# untitled.net
KiCad netlist of a schematic drawn in EAGLE
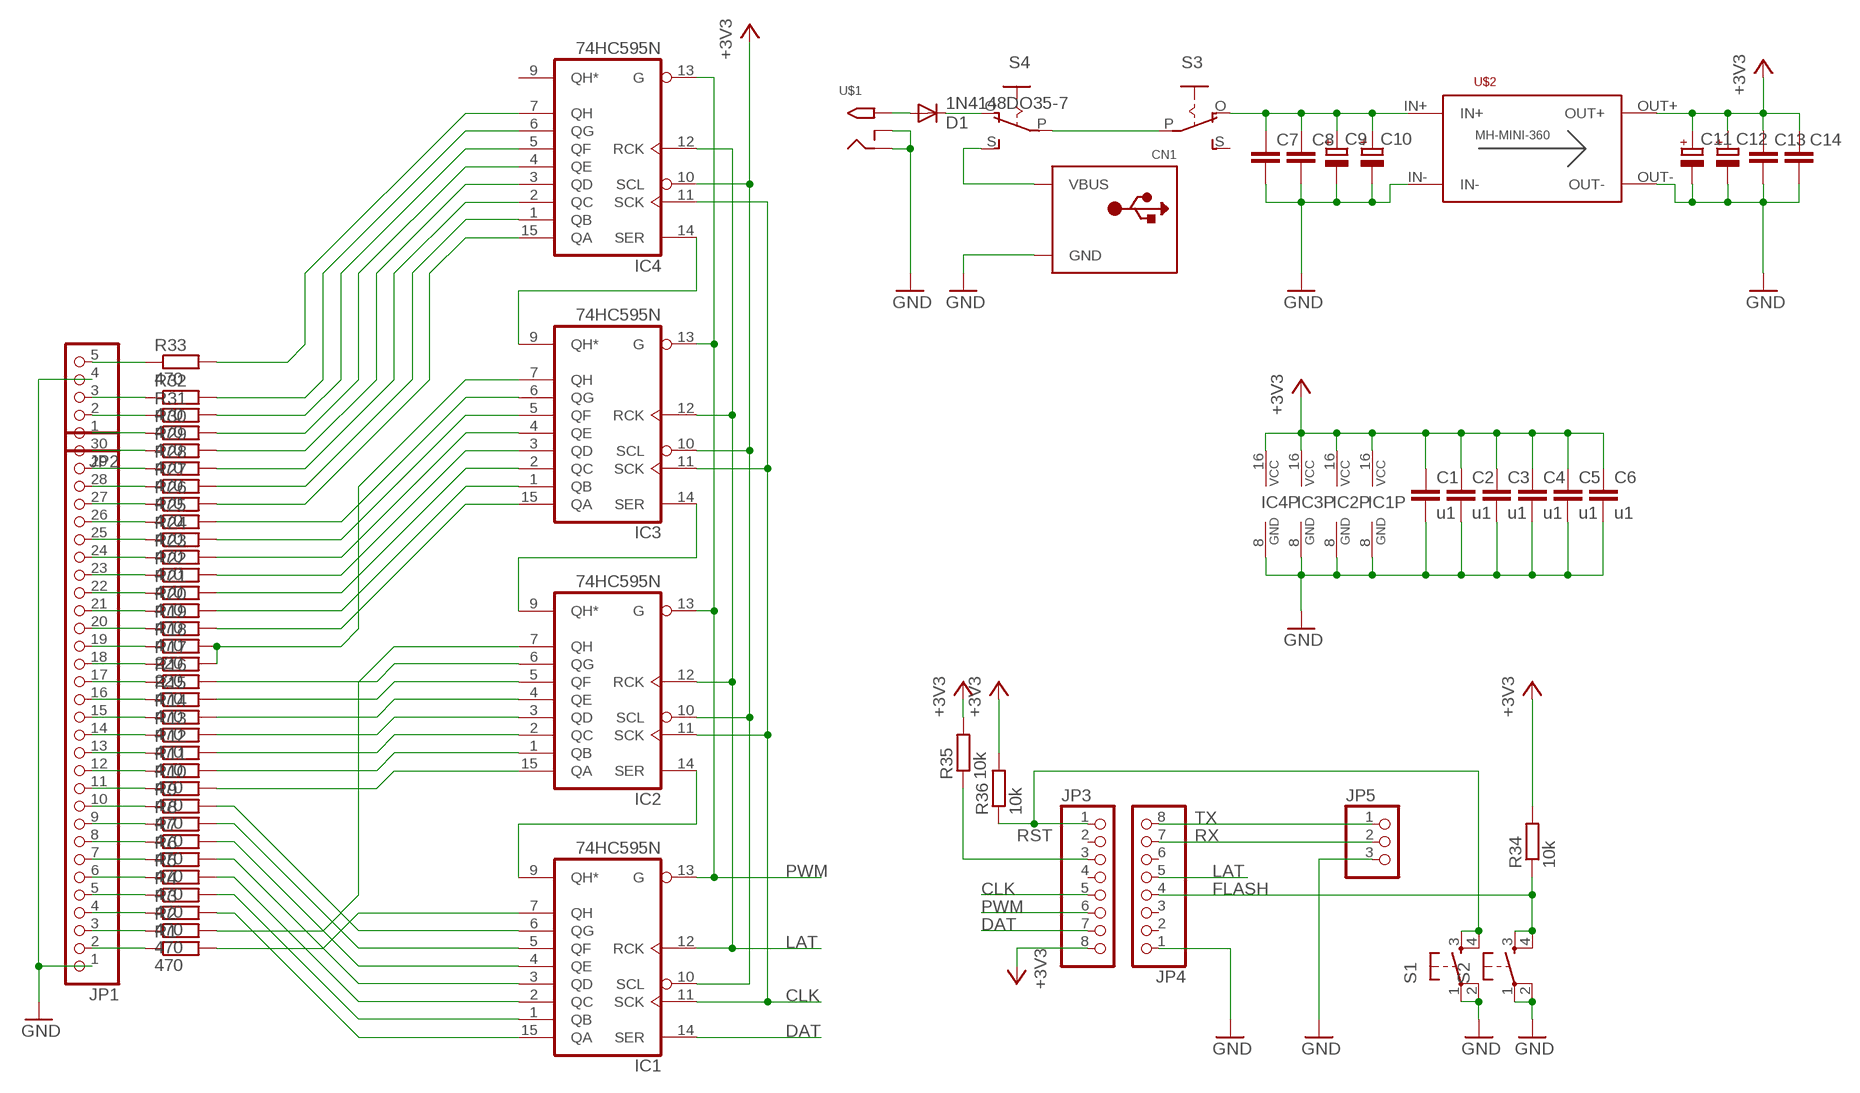
[diagram p0: schematic, sheet 1]

(export (version "E")
  (design (tool "Eeschema 10.0.6"))
  (components
    (comp (ref "C1")
      (value "u1")
      (footprint "eagle-import:C025-025X050")
      (libsource (lib "eagle-import") (part "C-EU025-025X050"))
    )
    (comp (ref "C2")
      (value "u1")
      (footprint "eagle-import:C025-025X050")
      (libsource (lib "eagle-import") (part "C-EU025-025X050"))
    )
    (comp (ref "C3")
      (value "u1")
      (footprint "eagle-import:C025-025X050")
      (libsource (lib "eagle-import") (part "C-EU025-025X050"))
    )
    (comp (ref "C4")
      (value "u1")
      (footprint "eagle-import:C025-025X050")
      (libsource (lib "eagle-import") (part "C-EU025-025X050"))
    )
    (comp (ref "C5")
      (value "u1")
      (footprint "eagle-import:C025-025X050")
      (libsource (lib "eagle-import") (part "C-EU025-025X050"))
    )
    (comp (ref "C6")
      (value "u1")
      (footprint "eagle-import:C025-025X050")
      (libsource (lib "eagle-import") (part "C-EU025-025X050"))
    )
    (comp (ref "C7")
      (value "C-EU025-025X050")
      (footprint "eagle-import:C025-025X050")
      (libsource (lib "eagle-import") (part "C-EU025-025X050"))
    )
    (comp (ref "C8")
      (value "C-EU025-025X050")
      (footprint "eagle-import:C025-025X050")
      (libsource (lib "eagle-import") (part "C-EU025-025X050"))
    )
    (comp (ref "C9")
      (value "CPOL-EUE2.5-7")
      (footprint "eagle-import:E2,5-7")
      (libsource (lib "eagle-import") (part "CPOL-EUE2.5-7"))
    )
    (comp (ref "C10")
      (value "CPOL-EUE2.5-7")
      (footprint "eagle-import:E2,5-7")
      (libsource (lib "eagle-import") (part "CPOL-EUE2.5-7"))
    )
    (comp (ref "C11")
      (value "CPOL-EUE2.5-7")
      (footprint "eagle-import:E2,5-7")
      (libsource (lib "eagle-import") (part "CPOL-EUE2.5-7"))
    )
    (comp (ref "C12")
      (value "CPOL-EUE2.5-7")
      (footprint "eagle-import:E2,5-7")
      (libsource (lib "eagle-import") (part "CPOL-EUE2.5-7"))
    )
    (comp (ref "C13")
      (value "C-EU025-025X050")
      (footprint "eagle-import:C025-025X050")
      (libsource (lib "eagle-import") (part "C-EU025-025X050"))
    )
    (comp (ref "C14")
      (value "C-EU025-025X050")
      (footprint "eagle-import:C025-025X050")
      (libsource (lib "eagle-import") (part "C-EU025-025X050"))
    )
    (comp (ref "CN1")
      (value "USBPWR-ONLY")
      (footprint "eagle-import:USB-MINIB-THM")
      (libsource (lib "eagle-import") (part "USBPWR-ONLY"))
    )
    (comp (ref "D1")
      (value "1N4148DO35-7")
      (footprint "eagle-import:DO35-7")
      (libsource (lib "eagle-import") (part "1N4148DO35-7"))
    )
    (comp (ref "IC1")
      (value "74HC595N")
      (footprint "eagle-import:DIL16")
      (libsource (lib "eagle-import") (part "74595NHC"))
    )
    (comp (ref "IC2")
      (value "74HC595N")
      (footprint "eagle-import:DIL16")
      (libsource (lib "eagle-import") (part "74595NHC"))
    )
    (comp (ref "IC3")
      (value "74HC595N")
      (footprint "eagle-import:DIL16")
      (libsource (lib "eagle-import") (part "74595NHC"))
    )
    (comp (ref "IC4")
      (value "74HC595N")
      (footprint "eagle-import:DIL16")
      (libsource (lib "eagle-import") (part "74595NHC"))
    )
    (comp (ref "JP1")
      (value "PINHD-1X30")
      (footprint "eagle-import:1X30")
      (libsource (lib "eagle-import") (part "PINHD-1X30"))
    )
    (comp (ref "JP2")
      (value "PINHD-1X5")
      (footprint "eagle-import:1X05")
      (libsource (lib "eagle-import") (part "PINHD-1X5"))
    )
    (comp (ref "JP3")
      (value "PINHD-1X8")
      (footprint "eagle-import:1X08")
      (libsource (lib "eagle-import") (part "PINHD-1X8"))
    )
    (comp (ref "JP4")
      (value "PINHD-1X8")
      (footprint "eagle-import:1X08")
      (libsource (lib "eagle-import") (part "PINHD-1X8"))
    )
    (comp (ref "JP5")
      (value "PINHD-1X3")
      (footprint "eagle-import:1X03")
      (libsource (lib "eagle-import") (part "PINHD-1X3"))
    )
    (comp (ref "R1")
      (value "470")
      (footprint "eagle-import:0204_5")
      (libsource (lib "eagle-import") (part "R-EU_0204/5"))
    )
    (comp (ref "R2")
      (value "470")
      (footprint "eagle-import:0204_5")
      (libsource (lib "eagle-import") (part "R-EU_0204/5"))
    )
    (comp (ref "R3")
      (value "470")
      (footprint "eagle-import:0204_5")
      (libsource (lib "eagle-import") (part "R-EU_0204/5"))
    )
    (comp (ref "R4")
      (value "470")
      (footprint "eagle-import:0204_5")
      (libsource (lib "eagle-import") (part "R-EU_0204/5"))
    )
    (comp (ref "R5")
      (value "470")
      (footprint "eagle-import:0204_5")
      (libsource (lib "eagle-import") (part "R-EU_0204/5"))
    )
    (comp (ref "R6")
      (value "470")
      (footprint "eagle-import:0204_5")
      (libsource (lib "eagle-import") (part "R-EU_0204/5"))
    )
    (comp (ref "R7")
      (value "470")
      (footprint "eagle-import:0204_5")
      (libsource (lib "eagle-import") (part "R-EU_0204/5"))
    )
    (comp (ref "R8")
      (value "470")
      (footprint "eagle-import:0204_5")
      (libsource (lib "eagle-import") (part "R-EU_0204/5"))
    )
    (comp (ref "R9")
      (value "470")
      (footprint "eagle-import:0204_5")
      (libsource (lib "eagle-import") (part "R-EU_0204/5"))
    )
    (comp (ref "R10")
      (value "470")
      (footprint "eagle-import:0204_5")
      (libsource (lib "eagle-import") (part "R-EU_0204/5"))
    )
    (comp (ref "R11")
      (value "470")
      (footprint "eagle-import:0204_5")
      (libsource (lib "eagle-import") (part "R-EU_0204/5"))
    )
    (comp (ref "R12")
      (value "470")
      (footprint "eagle-import:0204_5")
      (libsource (lib "eagle-import") (part "R-EU_0204/5"))
    )
    (comp (ref "R13")
      (value "470")
      (footprint "eagle-import:0204_5")
      (libsource (lib "eagle-import") (part "R-EU_0204/5"))
    )
    (comp (ref "R14")
      (value "470")
      (footprint "eagle-import:0204_5")
      (libsource (lib "eagle-import") (part "R-EU_0204/5"))
    )
    (comp (ref "R15")
      (value "470")
      (footprint "eagle-import:0204_5")
      (libsource (lib "eagle-import") (part "R-EU_0204/5"))
    )
    (comp (ref "R16")
      (value "470")
      (footprint "eagle-import:0204_5")
      (libsource (lib "eagle-import") (part "R-EU_0204/5"))
    )
    (comp (ref "R17")
      (value "220")
      (footprint "eagle-import:0204_5")
      (libsource (lib "eagle-import") (part "R-EU_0204/5"))
    )
    (comp (ref "R18")
      (value "220")
      (footprint "eagle-import:0204_5")
      (libsource (lib "eagle-import") (part "R-EU_0204/5"))
    )
    (comp (ref "R19")
      (value "470")
      (footprint "eagle-import:0204_5")
      (libsource (lib "eagle-import") (part "R-EU_0204/5"))
    )
    (comp (ref "R20")
      (value "470")
      (footprint "eagle-import:0204_5")
      (libsource (lib "eagle-import") (part "R-EU_0204/5"))
    )
    (comp (ref "R21")
      (value "470")
      (footprint "eagle-import:0204_5")
      (libsource (lib "eagle-import") (part "R-EU_0204/5"))
    )
    (comp (ref "R22")
      (value "470")
      (footprint "eagle-import:0204_5")
      (libsource (lib "eagle-import") (part "R-EU_0204/5"))
    )
    (comp (ref "R23")
      (value "470")
      (footprint "eagle-import:0204_5")
      (libsource (lib "eagle-import") (part "R-EU_0204/5"))
    )
    (comp (ref "R24")
      (value "470")
      (footprint "eagle-import:0204_5")
      (libsource (lib "eagle-import") (part "R-EU_0204/5"))
    )
    (comp (ref "R25")
      (value "470")
      (footprint "eagle-import:0204_5")
      (libsource (lib "eagle-import") (part "R-EU_0204/5"))
    )
    (comp (ref "R26")
      (value "470")
      (footprint "eagle-import:0204_5")
      (libsource (lib "eagle-import") (part "R-EU_0204/5"))
    )
    (comp (ref "R27")
      (value "470")
      (footprint "eagle-import:0204_5")
      (libsource (lib "eagle-import") (part "R-EU_0204/5"))
    )
    (comp (ref "R28")
      (value "470")
      (footprint "eagle-import:0204_5")
      (libsource (lib "eagle-import") (part "R-EU_0204/5"))
    )
    (comp (ref "R29")
      (value "470")
      (footprint "eagle-import:0204_5")
      (libsource (lib "eagle-import") (part "R-EU_0204/5"))
    )
    (comp (ref "R30")
      (value "470")
      (footprint "eagle-import:0204_5")
      (libsource (lib "eagle-import") (part "R-EU_0204/5"))
    )
    (comp (ref "R31")
      (value "470")
      (footprint "eagle-import:0204_5")
      (libsource (lib "eagle-import") (part "R-EU_0204/5"))
    )
    (comp (ref "R32")
      (value "470")
      (footprint "eagle-import:0204_5")
      (libsource (lib "eagle-import") (part "R-EU_0204/5"))
    )
    (comp (ref "R33")
      (value "470")
      (footprint "eagle-import:0204_5")
      (libsource (lib "eagle-import") (part "R-EU_0204/5"))
    )
    (comp (ref "R34")
      (value "10k")
      (footprint "eagle-import:0204_7")
      (libsource (lib "eagle-import") (part "R-EU_0204/7"))
    )
    (comp (ref "R35")
      (value "10k")
      (footprint "eagle-import:0207_10")
      (libsource (lib "eagle-import") (part "R-EU_0207/10"))
    )
    (comp (ref "R36")
      (value "10k")
      (footprint "eagle-import:0207_10")
      (libsource (lib "eagle-import") (part "R-EU_0207/10"))
    )
    (comp (ref "S1")
      (value "TAC_SWITCHPTH")
      (footprint "eagle-import:TACTILE-PTH")
      (libsource (lib "eagle-import") (part "TAC_SWITCHPTH"))
    )
    (comp (ref "S2")
      (value "TAC_SWITCHPTH")
      (footprint "eagle-import:TACTILE-PTH")
      (libsource (lib "eagle-import") (part "TAC_SWITCHPTH"))
    )
    (comp (ref "S3")
      (value "EG1218S")
      (footprint "eagle-import:EG1218")
      (libsource (lib "eagle-import") (part "EG1218S"))
    )
    (comp (ref "S4")
      (value "EG1218S")
      (footprint "eagle-import:EG1218")
      (libsource (lib "eagle-import") (part "EG1218S"))
    )
    (comp (ref "U$1")
      (value "2.1MMJACKTHM")
      (footprint "eagle-import:PJ-102A")
      (libsource (lib "eagle-import") (part "2.1MMJACKTHM"))
    )
    (comp (ref "U$2")
      (value "DC-DC_CONV_MINISTD")
      (footprint "eagle-import:DC-DC_CONV_MINI")
      (libsource (lib "eagle-import") (part "DC-DC_CONV_MINISTD"))
    )
  )
  (nets
    (net (code "1") (name "+3V3") (class "Default")
      (node (ref "C1") (pin "1") (pinfunction "1_1") (pintype "passive"))
      (node (ref "C11") (pin "+") (pinfunction "+_+") (pintype "passive"))
      (node (ref "C12") (pin "+") (pinfunction "+_+") (pintype "passive"))
      (node (ref "C13") (pin "1") (pinfunction "1_1") (pintype "passive"))
      (node (ref "C14") (pin "1") (pinfunction "1_1") (pintype "passive"))
      (node (ref "C2") (pin "1") (pinfunction "1_1") (pintype "passive"))
      (node (ref "C3") (pin "1") (pinfunction "1_1") (pintype "passive"))
      (node (ref "C4") (pin "1") (pinfunction "1_1") (pintype "passive"))
      (node (ref "C5") (pin "1") (pinfunction "1_1") (pintype "passive"))
      (node (ref "C6") (pin "1") (pinfunction "1_1") (pintype "passive"))
      (node (ref "IC1") (pin "10") (pinfunction "SCL_10") (pintype "input"))
      (node (ref "IC1") (pin "16") (pinfunction "VCC_16") (pintype "power_in"))
      (node (ref "IC2") (pin "10") (pinfunction "SCL_10") (pintype "input"))
      (node (ref "IC2") (pin "16") (pinfunction "VCC_16") (pintype "power_in"))
      (node (ref "IC3") (pin "10") (pinfunction "SCL_10") (pintype "input"))
      (node (ref "IC3") (pin "16") (pinfunction "VCC_16") (pintype "power_in"))
      (node (ref "IC4") (pin "10") (pinfunction "SCL_10") (pintype "input"))
      (node (ref "IC4") (pin "16") (pinfunction "VCC_16") (pintype "power_in"))
      (node (ref "JP3") (pin "8") (pinfunction "8_8") (pintype "passive"))
      (node (ref "R34") (pin "2") (pinfunction "2_2") (pintype "passive"))
      (node (ref "R35") (pin "2") (pinfunction "2_2") (pintype "passive"))
      (node (ref "R36") (pin "2") (pinfunction "2_2") (pintype "passive"))
      (node (ref "U$2") (pin "OUT+") (pinfunction "OUT+_OUT+") (pintype "bidirectional"))
    )
    (net (code "2") (name "/CLK") (class "Default")
      (node (ref "IC1") (pin "11") (pinfunction "SCK_11") (pintype "input"))
      (node (ref "IC2") (pin "11") (pinfunction "SCK_11") (pintype "input"))
      (node (ref "IC3") (pin "11") (pinfunction "SCK_11") (pintype "input"))
      (node (ref "IC4") (pin "11") (pinfunction "SCK_11") (pintype "input"))
      (node (ref "JP3") (pin "5") (pinfunction "5_5") (pintype "passive"))
    )
    (net (code "3") (name "/DAT") (class "Default")
      (node (ref "IC1") (pin "14") (pinfunction "SER_14") (pintype "input"))
      (node (ref "JP3") (pin "7") (pinfunction "7_7") (pintype "passive"))
    )
    (net (code "4") (name "/FLASH") (class "Default")
      (node (ref "JP4") (pin "4") (pinfunction "4_4") (pintype "passive"))
      (node (ref "R34") (pin "1") (pinfunction "1_1") (pintype "passive"))
      (node (ref "S2") (pin "3") (pinfunction "3_3") (pintype "passive"))
      (node (ref "S2") (pin "4") (pinfunction "4_4") (pintype "passive"))
    )
    (net (code "5") (name "/LAT") (class "Default")
      (node (ref "IC1") (pin "12") (pinfunction "RCK_12") (pintype "input"))
      (node (ref "IC2") (pin "12") (pinfunction "RCK_12") (pintype "input"))
      (node (ref "IC3") (pin "12") (pinfunction "RCK_12") (pintype "input"))
      (node (ref "IC4") (pin "12") (pinfunction "RCK_12") (pintype "input"))
      (node (ref "JP4") (pin "5") (pinfunction "5_5") (pintype "passive"))
    )
    (net (code "6") (name "/PWM") (class "Default")
      (node (ref "IC1") (pin "13") (pinfunction "G_13") (pintype "input"))
      (node (ref "IC2") (pin "13") (pinfunction "G_13") (pintype "input"))
      (node (ref "IC3") (pin "13") (pinfunction "G_13") (pintype "input"))
      (node (ref "IC4") (pin "13") (pinfunction "G_13") (pintype "input"))
      (node (ref "JP3") (pin "6") (pinfunction "6_6") (pintype "passive"))
    )
    (net (code "7") (name "/RST") (class "Default")
      (node (ref "JP3") (pin "1") (pinfunction "1_1") (pintype "passive"))
      (node (ref "R36") (pin "1") (pinfunction "1_1") (pintype "passive"))
      (node (ref "S1") (pin "3") (pinfunction "3_3") (pintype "passive"))
      (node (ref "S1") (pin "4") (pinfunction "4_4") (pintype "passive"))
    )
    (net (code "8") (name "/RX") (class "Default")
      (node (ref "JP4") (pin "7") (pinfunction "7_7") (pintype "passive"))
      (node (ref "JP5") (pin "2") (pinfunction "2_2") (pintype "passive"))
    )
    (net (code "9") (name "/TX") (class "Default")
      (node (ref "JP4") (pin "8") (pinfunction "8_8") (pintype "passive"))
      (node (ref "JP5") (pin "1") (pinfunction "1_1") (pintype "passive"))
    )
    (net (code "10") (name "GND") (class "Default")
      (node (ref "C1") (pin "2") (pinfunction "2_2") (pintype "passive"))
      (node (ref "C10") (pin "-") (pinfunction "-_-") (pintype "passive"))
      (node (ref "C11") (pin "-") (pinfunction "-_-") (pintype "passive"))
      (node (ref "C12") (pin "-") (pinfunction "-_-") (pintype "passive"))
      (node (ref "C13") (pin "2") (pinfunction "2_2") (pintype "passive"))
      (node (ref "C14") (pin "2") (pinfunction "2_2") (pintype "passive"))
      (node (ref "C2") (pin "2") (pinfunction "2_2") (pintype "passive"))
      (node (ref "C3") (pin "2") (pinfunction "2_2") (pintype "passive"))
      (node (ref "C4") (pin "2") (pinfunction "2_2") (pintype "passive"))
      (node (ref "C5") (pin "2") (pinfunction "2_2") (pintype "passive"))
      (node (ref "C6") (pin "2") (pinfunction "2_2") (pintype "passive"))
      (node (ref "C7") (pin "2") (pinfunction "2_2") (pintype "passive"))
      (node (ref "C8") (pin "2") (pinfunction "2_2") (pintype "passive"))
      (node (ref "C9") (pin "-") (pinfunction "-_-") (pintype "passive"))
      (node (ref "CN1") (pin "GND") (pinfunction "GND_GND") (pintype "power_in"))
      (node (ref "CN1") (pin "GND1") (pinfunction "GND_GND1") (pintype "power_in"))
      (node (ref "CN1") (pin "GND2") (pinfunction "GND_GND2") (pintype "power_in"))
      (node (ref "CN1") (pin "GND3") (pinfunction "GND_GND3") (pintype "power_in"))
      (node (ref "CN1") (pin "GND4") (pinfunction "GND_GND4") (pintype "power_in"))
      (node (ref "IC1") (pin "8") (pinfunction "GND_8") (pintype "power_in"))
      (node (ref "IC2") (pin "8") (pinfunction "GND_8") (pintype "power_in"))
      (node (ref "IC3") (pin "8") (pinfunction "GND_8") (pintype "power_in"))
      (node (ref "IC4") (pin "8") (pinfunction "GND_8") (pintype "power_in"))
      (node (ref "JP1") (pin "1") (pinfunction "1_1") (pintype "passive"))
      (node (ref "JP2") (pin "4") (pinfunction "4_4") (pintype "passive"))
      (node (ref "JP4") (pin "1") (pinfunction "1_1") (pintype "passive"))
      (node (ref "JP5") (pin "3") (pinfunction "3_3") (pintype "passive"))
      (node (ref "S1") (pin "1") (pinfunction "1_1") (pintype "passive"))
      (node (ref "S1") (pin "2") (pinfunction "2_2") (pintype "passive"))
      (node (ref "S2") (pin "1") (pinfunction "1_1") (pintype "passive"))
      (node (ref "S2") (pin "2") (pinfunction "2_2") (pintype "passive"))
      (node (ref "U$1") (pin "RING") (pinfunction "RING_RING") (pintype "bidirectional"))
      (node (ref "U$1") (pin "RING_SW") (pinfunction "RING_SW_RING_SW") (pintype "bidirectional"))
      (node (ref "U$2") (pin "IN-") (pinfunction "IN-_IN-") (pintype "bidirectional"))
      (node (ref "U$2") (pin "OUT-") (pinfunction "OUT-_OUT-") (pintype "bidirectional"))
    )
    (net (code "11") (name "Net-(C10-Pad+)") (class "Default")
      (node (ref "C10") (pin "+") (pinfunction "+_+") (pintype "passive"))
      (node (ref "C7") (pin "1") (pinfunction "1_1") (pintype "passive"))
      (node (ref "C8") (pin "1") (pinfunction "1_1") (pintype "passive"))
      (node (ref "C9") (pin "+") (pinfunction "+_+") (pintype "passive"))
      (node (ref "S3") (pin "O") (pinfunction "O_O") (pintype "passive"))
      (node (ref "U$2") (pin "IN+") (pinfunction "IN+_IN+") (pintype "bidirectional"))
    )
    (net (code "12") (name "Net-(CN1-PadVBUS)") (class "Default")
      (node (ref "CN1") (pin "VBUS") (pinfunction "VBUS_VBUS") (pintype "power_in"))
      (node (ref "S4") (pin "S") (pinfunction "S_S") (pintype "passive"))
    )
    (net (code "13") (name "Net-(D1-PadA)") (class "Default")
      (node (ref "D1") (pin "A") (pinfunction "A_A") (pintype "passive"))
      (node (ref "U$1") (pin "TIP") (pinfunction "TIP_TIP") (pintype "bidirectional"))
    )
    (net (code "14") (name "Net-(D1-PadC)") (class "Default")
      (node (ref "D1") (pin "C") (pinfunction "C_C") (pintype "passive"))
      (node (ref "S4") (pin "O") (pinfunction "O_O") (pintype "passive"))
    )
    (net (code "15") (name "Net-(IC1A-QA)") (class "Default")
      (node (ref "IC1") (pin "15") (pinfunction "QA_15") (pintype "tri_state"))
      (node (ref "R3") (pin "2") (pinfunction "2_2") (pintype "passive"))
    )
    (net (code "16") (name "Net-(IC1A-QB)") (class "Default")
      (node (ref "IC1") (pin "1") (pinfunction "QB_1") (pintype "tri_state"))
      (node (ref "R4") (pin "2") (pinfunction "2_2") (pintype "passive"))
    )
    (net (code "17") (name "Net-(IC1A-QC)") (class "Default")
      (node (ref "IC1") (pin "2") (pinfunction "QC_2") (pintype "tri_state"))
      (node (ref "R5") (pin "2") (pinfunction "2_2") (pintype "passive"))
    )
    (net (code "18") (name "Net-(IC1A-QD)") (class "Default")
      (node (ref "IC1") (pin "3") (pinfunction "QD_3") (pintype "tri_state"))
      (node (ref "R6") (pin "2") (pinfunction "2_2") (pintype "passive"))
    )
    (net (code "19") (name "Net-(IC1A-QE)") (class "Default")
      (node (ref "IC1") (pin "4") (pinfunction "QE_4") (pintype "tri_state"))
      (node (ref "R7") (pin "2") (pinfunction "2_2") (pintype "passive"))
    )
    (net (code "20") (name "Net-(IC1A-QF)") (class "Default")
      (node (ref "IC1") (pin "5") (pinfunction "QF_5") (pintype "tri_state"))
      (node (ref "R8") (pin "2") (pinfunction "2_2") (pintype "passive"))
    )
    (net (code "21") (name "Net-(IC1A-QG)") (class "Default")
      (node (ref "IC1") (pin "6") (pinfunction "QG_6") (pintype "tri_state"))
      (node (ref "R9") (pin "2") (pinfunction "2_2") (pintype "passive"))
    )
    (net (code "22") (name "Net-(IC1A-QH)") (class "Default")
      (node (ref "IC1") (pin "7") (pinfunction "QH_7") (pintype "tri_state"))
      (node (ref "R1") (pin "2") (pinfunction "2_2") (pintype "passive"))
    )
    (net (code "23") (name "Net-(IC1A-QH*)") (class "Default")
      (node (ref "IC1") (pin "9") (pinfunction "QH*_9") (pintype "tri_state"))
      (node (ref "IC2") (pin "14") (pinfunction "SER_14") (pintype "input"))
    )
    (net (code "24") (name "Net-(IC2A-QA)") (class "Default")
      (node (ref "IC2") (pin "15") (pinfunction "QA_15") (pintype "tri_state"))
      (node (ref "R10") (pin "2") (pinfunction "2_2") (pintype "passive"))
    )
    (net (code "25") (name "Net-(IC2A-QB)") (class "Default")
      (node (ref "IC2") (pin "1") (pinfunction "QB_1") (pintype "tri_state"))
      (node (ref "R11") (pin "2") (pinfunction "2_2") (pintype "passive"))
    )
    (net (code "26") (name "Net-(IC2A-QC)") (class "Default")
      (node (ref "IC2") (pin "2") (pinfunction "QC_2") (pintype "tri_state"))
      (node (ref "R12") (pin "2") (pinfunction "2_2") (pintype "passive"))
    )
    (net (code "27") (name "Net-(IC2A-QD)") (class "Default")
      (node (ref "IC2") (pin "3") (pinfunction "QD_3") (pintype "tri_state"))
      (node (ref "R13") (pin "2") (pinfunction "2_2") (pintype "passive"))
    )
    (net (code "28") (name "Net-(IC2A-QE)") (class "Default")
      (node (ref "IC2") (pin "4") (pinfunction "QE_4") (pintype "tri_state"))
      (node (ref "R14") (pin "2") (pinfunction "2_2") (pintype "passive"))
    )
    (net (code "29") (name "Net-(IC2A-QF)") (class "Default")
      (node (ref "IC2") (pin "5") (pinfunction "QF_5") (pintype "tri_state"))
      (node (ref "R15") (pin "2") (pinfunction "2_2") (pintype "passive"))
    )
    (net (code "30") (name "Net-(IC2A-QG)") (class "Default")
      (node (ref "IC2") (pin "6") (pinfunction "QG_6") (pintype "tri_state"))
      (node (ref "R16") (pin "2") (pinfunction "2_2") (pintype "passive"))
    )
    (net (code "31") (name "Net-(IC2A-QH)") (class "Default")
      (node (ref "IC2") (pin "7") (pinfunction "QH_7") (pintype "tri_state"))
      (node (ref "R2") (pin "2") (pinfunction "2_2") (pintype "passive"))
    )
    (net (code "32") (name "Net-(IC2A-QH*)") (class "Default")
      (node (ref "IC2") (pin "9") (pinfunction "QH*_9") (pintype "tri_state"))
      (node (ref "IC3") (pin "14") (pinfunction "SER_14") (pintype "input"))
    )
    (net (code "33") (name "Net-(IC3A-QA)") (class "Default")
      (node (ref "IC3") (pin "15") (pinfunction "QA_15") (pintype "tri_state"))
      (node (ref "R19") (pin "2") (pinfunction "2_2") (pintype "passive"))
    )
    (net (code "34") (name "Net-(IC3A-QB)") (class "Default")
      (node (ref "IC3") (pin "1") (pinfunction "QB_1") (pintype "tri_state"))
      (node (ref "R20") (pin "2") (pinfunction "2_2") (pintype "passive"))
    )
    (net (code "35") (name "Net-(IC3A-QC)") (class "Default")
      (node (ref "IC3") (pin "2") (pinfunction "QC_2") (pintype "tri_state"))
      (node (ref "R21") (pin "2") (pinfunction "2_2") (pintype "passive"))
    )
    (net (code "36") (name "Net-(IC3A-QD)") (class "Default")
      (node (ref "IC3") (pin "3") (pinfunction "QD_3") (pintype "tri_state"))
      (node (ref "R22") (pin "2") (pinfunction "2_2") (pintype "passive"))
    )
    (net (code "37") (name "Net-(IC3A-QE)") (class "Default")
      (node (ref "IC3") (pin "4") (pinfunction "QE_4") (pintype "tri_state"))
      (node (ref "R23") (pin "2") (pinfunction "2_2") (pintype "passive"))
    )
    (net (code "38") (name "Net-(IC3A-QF)") (class "Default")
      (node (ref "IC3") (pin "5") (pinfunction "QF_5") (pintype "tri_state"))
      (node (ref "R24") (pin "2") (pinfunction "2_2") (pintype "passive"))
    )
    (net (code "39") (name "Net-(IC3A-QG)") (class "Default")
      (node (ref "IC3") (pin "6") (pinfunction "QG_6") (pintype "tri_state"))
      (node (ref "R25") (pin "2") (pinfunction "2_2") (pintype "passive"))
    )
    (net (code "40") (name "Net-(IC3A-QH)") (class "Default")
      (node (ref "IC3") (pin "7") (pinfunction "QH_7") (pintype "tri_state"))
      (node (ref "R17") (pin "2") (pinfunction "2_2") (pintype "passive"))
      (node (ref "R18") (pin "2") (pinfunction "2_2") (pintype "passive"))
    )
    (net (code "41") (name "Net-(IC3A-QH*)") (class "Default")
      (node (ref "IC3") (pin "9") (pinfunction "QH*_9") (pintype "tri_state"))
      (node (ref "IC4") (pin "14") (pinfunction "SER_14") (pintype "input"))
    )
    (net (code "42") (name "Net-(IC4A-QA)") (class "Default")
      (node (ref "IC4") (pin "15") (pinfunction "QA_15") (pintype "tri_state"))
      (node (ref "R26") (pin "2") (pinfunction "2_2") (pintype "passive"))
    )
    (net (code "43") (name "Net-(IC4A-QB)") (class "Default")
      (node (ref "IC4") (pin "1") (pinfunction "QB_1") (pintype "tri_state"))
      (node (ref "R27") (pin "2") (pinfunction "2_2") (pintype "passive"))
    )
    (net (code "44") (name "Net-(IC4A-QC)") (class "Default")
      (node (ref "IC4") (pin "2") (pinfunction "QC_2") (pintype "tri_state"))
      (node (ref "R28") (pin "2") (pinfunction "2_2") (pintype "passive"))
    )
    (net (code "45") (name "Net-(IC4A-QD)") (class "Default")
      (node (ref "IC4") (pin "3") (pinfunction "QD_3") (pintype "tri_state"))
      (node (ref "R29") (pin "2") (pinfunction "2_2") (pintype "passive"))
    )
    (net (code "46") (name "Net-(IC4A-QE)") (class "Default")
      (node (ref "IC4") (pin "4") (pinfunction "QE_4") (pintype "tri_state"))
      (node (ref "R30") (pin "2") (pinfunction "2_2") (pintype "passive"))
    )
    (net (code "47") (name "Net-(IC4A-QF)") (class "Default")
      (node (ref "IC4") (pin "5") (pinfunction "QF_5") (pintype "tri_state"))
      (node (ref "R31") (pin "2") (pinfunction "2_2") (pintype "passive"))
    )
    (net (code "48") (name "Net-(IC4A-QG)") (class "Default")
      (node (ref "IC4") (pin "6") (pinfunction "QG_6") (pintype "tri_state"))
      (node (ref "R32") (pin "2") (pinfunction "2_2") (pintype "passive"))
    )
    (net (code "49") (name "Net-(IC4A-QH)") (class "Default")
      (node (ref "IC4") (pin "7") (pinfunction "QH_7") (pintype "tri_state"))
      (node (ref "R33") (pin "2") (pinfunction "2_2") (pintype "passive"))
    )
    (net (code "50") (name "Net-(JP1-Pad2)") (class "Default")
      (node (ref "JP1") (pin "2") (pinfunction "2_2") (pintype "passive"))
      (node (ref "R1") (pin "1") (pinfunction "1_1") (pintype "passive"))
    )
    (net (code "51") (name "Net-(JP1-Pad3)") (class "Default")
      (node (ref "JP1") (pin "3") (pinfunction "3_3") (pintype "passive"))
      (node (ref "R2") (pin "1") (pinfunction "1_1") (pintype "passive"))
    )
    (net (code "52") (name "Net-(JP1-Pad4)") (class "Default")
      (node (ref "JP1") (pin "4") (pinfunction "4_4") (pintype "passive"))
      (node (ref "R3") (pin "1") (pinfunction "1_1") (pintype "passive"))
    )
    (net (code "53") (name "Net-(JP1-Pad5)") (class "Default")
      (node (ref "JP1") (pin "5") (pinfunction "5_5") (pintype "passive"))
      (node (ref "R4") (pin "1") (pinfunction "1_1") (pintype "passive"))
    )
    (net (code "54") (name "Net-(JP1-Pad6)") (class "Default")
      (node (ref "JP1") (pin "6") (pinfunction "6_6") (pintype "passive"))
      (node (ref "R5") (pin "1") (pinfunction "1_1") (pintype "passive"))
    )
    (net (code "55") (name "Net-(JP1-Pad7)") (class "Default")
      (node (ref "JP1") (pin "7") (pinfunction "7_7") (pintype "passive"))
      (node (ref "R6") (pin "1") (pinfunction "1_1") (pintype "passive"))
    )
    (net (code "56") (name "Net-(JP1-Pad8)") (class "Default")
      (node (ref "JP1") (pin "8") (pinfunction "8_8") (pintype "passive"))
      (node (ref "R7") (pin "1") (pinfunction "1_1") (pintype "passive"))
    )
    (net (code "57") (name "Net-(JP1-Pad9)") (class "Default")
      (node (ref "JP1") (pin "9") (pinfunction "9_9") (pintype "passive"))
      (node (ref "R8") (pin "1") (pinfunction "1_1") (pintype "passive"))
    )
    (net (code "58") (name "Net-(JP1-Pad10)") (class "Default")
      (node (ref "JP1") (pin "10") (pinfunction "10_10") (pintype "passive"))
      (node (ref "R9") (pin "1") (pinfunction "1_1") (pintype "passive"))
    )
    (net (code "59") (name "Net-(JP1-Pad11)") (class "Default")
      (node (ref "JP1") (pin "11") (pinfunction "11_11") (pintype "passive"))
      (node (ref "R10") (pin "1") (pinfunction "1_1") (pintype "passive"))
    )
    (net (code "60") (name "Net-(JP1-Pad12)") (class "Default")
      (node (ref "JP1") (pin "12") (pinfunction "12_12") (pintype "passive"))
      (node (ref "R11") (pin "1") (pinfunction "1_1") (pintype "passive"))
    )
    (net (code "61") (name "Net-(JP1-Pad13)") (class "Default")
      (node (ref "JP1") (pin "13") (pinfunction "13_13") (pintype "passive"))
      (node (ref "R12") (pin "1") (pinfunction "1_1") (pintype "passive"))
    )
    (net (code "62") (name "Net-(JP1-Pad14)") (class "Default")
      (node (ref "JP1") (pin "14") (pinfunction "14_14") (pintype "passive"))
      (node (ref "R13") (pin "1") (pinfunction "1_1") (pintype "passive"))
    )
    (net (code "63") (name "Net-(JP1-Pad15)") (class "Default")
      (node (ref "JP1") (pin "15") (pinfunction "15_15") (pintype "passive"))
      (node (ref "R14") (pin "1") (pinfunction "1_1") (pintype "passive"))
    )
    (net (code "64") (name "Net-(JP1-Pad16)") (class "Default")
      (node (ref "JP1") (pin "16") (pinfunction "16_16") (pintype "passive"))
      (node (ref "R15") (pin "1") (pinfunction "1_1") (pintype "passive"))
    )
    (net (code "65") (name "Net-(JP1-Pad17)") (class "Default")
      (node (ref "JP1") (pin "17") (pinfunction "17_17") (pintype "passive"))
      (node (ref "R16") (pin "1") (pinfunction "1_1") (pintype "passive"))
    )
    (net (code "66") (name "Net-(JP1-Pad18)") (class "Default")
      (node (ref "JP1") (pin "18") (pinfunction "18_18") (pintype "passive"))
      (node (ref "R17") (pin "1") (pinfunction "1_1") (pintype "passive"))
    )
    (net (code "67") (name "Net-(JP1-Pad19)") (class "Default")
      (node (ref "JP1") (pin "19") (pinfunction "19_19") (pintype "passive"))
      (node (ref "R18") (pin "1") (pinfunction "1_1") (pintype "passive"))
    )
    (net (code "68") (name "Net-(JP1-Pad20)") (class "Default")
      (node (ref "JP1") (pin "20") (pinfunction "20_20") (pintype "passive"))
      (node (ref "R19") (pin "1") (pinfunction "1_1") (pintype "passive"))
    )
    (net (code "69") (name "Net-(JP1-Pad21)") (class "Default")
      (node (ref "JP1") (pin "21") (pinfunction "21_21") (pintype "passive"))
      (node (ref "R20") (pin "1") (pinfunction "1_1") (pintype "passive"))
    )
    (net (code "70") (name "Net-(JP1-Pad22)") (class "Default")
      (node (ref "JP1") (pin "22") (pinfunction "22_22") (pintype "passive"))
      (node (ref "R21") (pin "1") (pinfunction "1_1") (pintype "passive"))
    )
    (net (code "71") (name "Net-(JP1-Pad23)") (class "Default")
      (node (ref "JP1") (pin "23") (pinfunction "23_23") (pintype "passive"))
      (node (ref "R22") (pin "1") (pinfunction "1_1") (pintype "passive"))
    )
    (net (code "72") (name "Net-(JP1-Pad24)") (class "Default")
      (node (ref "JP1") (pin "24") (pinfunction "24_24") (pintype "passive"))
      (node (ref "R23") (pin "1") (pinfunction "1_1") (pintype "passive"))
    )
    (net (code "73") (name "Net-(JP1-Pad25)") (class "Default")
      (node (ref "JP1") (pin "25") (pinfunction "25_25") (pintype "passive"))
      (node (ref "R24") (pin "1") (pinfunction "1_1") (pintype "passive"))
    )
    (net (code "74") (name "Net-(JP1-Pad26)") (class "Default")
      (node (ref "JP1") (pin "26") (pinfunction "26_26") (pintype "passive"))
      (node (ref "R25") (pin "1") (pinfunction "1_1") (pintype "passive"))
    )
    (net (code "75") (name "Net-(JP1-Pad27)") (class "Default")
      (node (ref "JP1") (pin "27") (pinfunction "27_27") (pintype "passive"))
      (node (ref "R26") (pin "1") (pinfunction "1_1") (pintype "passive"))
    )
    (net (code "76") (name "Net-(JP1-Pad28)") (class "Default")
      (node (ref "JP1") (pin "28") (pinfunction "28_28") (pintype "passive"))
      (node (ref "R27") (pin "1") (pinfunction "1_1") (pintype "passive"))
    )
    (net (code "77") (name "Net-(JP1-Pad29)") (class "Default")
      (node (ref "JP1") (pin "29") (pinfunction "29_29") (pintype "passive"))
      (node (ref "R28") (pin "1") (pinfunction "1_1") (pintype "passive"))
    )
    (net (code "78") (name "Net-(JP1-Pad30)") (class "Default")
      (node (ref "JP1") (pin "30") (pinfunction "30_30") (pintype "passive"))
      (node (ref "R29") (pin "1") (pinfunction "1_1") (pintype "passive"))
    )
    (net (code "79") (name "Net-(JP2-Pad1)") (class "Default")
      (node (ref "JP2") (pin "1") (pinfunction "1_1") (pintype "passive"))
      (node (ref "R30") (pin "1") (pinfunction "1_1") (pintype "passive"))
    )
    (net (code "80") (name "Net-(JP2-Pad2)") (class "Default")
      (node (ref "JP2") (pin "2") (pinfunction "2_2") (pintype "passive"))
      (node (ref "R31") (pin "1") (pinfunction "1_1") (pintype "passive"))
    )
    (net (code "81") (name "Net-(JP2-Pad3)") (class "Default")
      (node (ref "JP2") (pin "3") (pinfunction "3_3") (pintype "passive"))
      (node (ref "R32") (pin "1") (pinfunction "1_1") (pintype "passive"))
    )
    (net (code "82") (name "Net-(JP2-Pad5)") (class "Default")
      (node (ref "JP2") (pin "5") (pinfunction "5_5") (pintype "passive"))
      (node (ref "R33") (pin "1") (pinfunction "1_1") (pintype "passive"))
    )
    (net (code "83") (name "Net-(JP3-Pad3)") (class "Default")
      (node (ref "JP3") (pin "3") (pinfunction "3_3") (pintype "passive"))
      (node (ref "R35") (pin "1") (pinfunction "1_1") (pintype "passive"))
    )
    (net (code "84") (name "Net-(S3-PadP)") (class "Default")
      (node (ref "S3") (pin "P") (pinfunction "P_P") (pintype "passive"))
      (node (ref "S4") (pin "P") (pinfunction "P_P") (pintype "passive"))
    )
    (net (code "85") (name "unconnected-(IC4A-QH*-Pad9)") (class "Default")
      (node (ref "IC4") (pin "9") (pinfunction "QH*_9") (pintype "tri_state"))
    )
    (net (code "86") (name "unconnected-(JP3-Pad2)") (class "Default")
      (node (ref "JP3") (pin "2") (pinfunction "2_2") (pintype "passive"))
    )
    (net (code "87") (name "unconnected-(JP3-Pad4)") (class "Default")
      (node (ref "JP3") (pin "4") (pinfunction "4_4") (pintype "passive"))
    )
    (net (code "88") (name "unconnected-(JP4-Pad2)") (class "Default")
      (node (ref "JP4") (pin "2") (pinfunction "2_2") (pintype "passive"))
    )
    (net (code "89") (name "unconnected-(JP4-Pad3)") (class "Default")
      (node (ref "JP4") (pin "3") (pinfunction "3_3") (pintype "passive"))
    )
    (net (code "90") (name "unconnected-(JP4-Pad6)") (class "Default")
      (node (ref "JP4") (pin "6") (pinfunction "6_6") (pintype "passive"))
    )
    (net (code "91") (name "unconnected-(S3-PadS)") (class "Default")
      (node (ref "S3") (pin "S") (pinfunction "S_S") (pintype "passive"))
    )
  )
)
